# controller.net
KiCad netlist of a schematic drawn in EAGLE
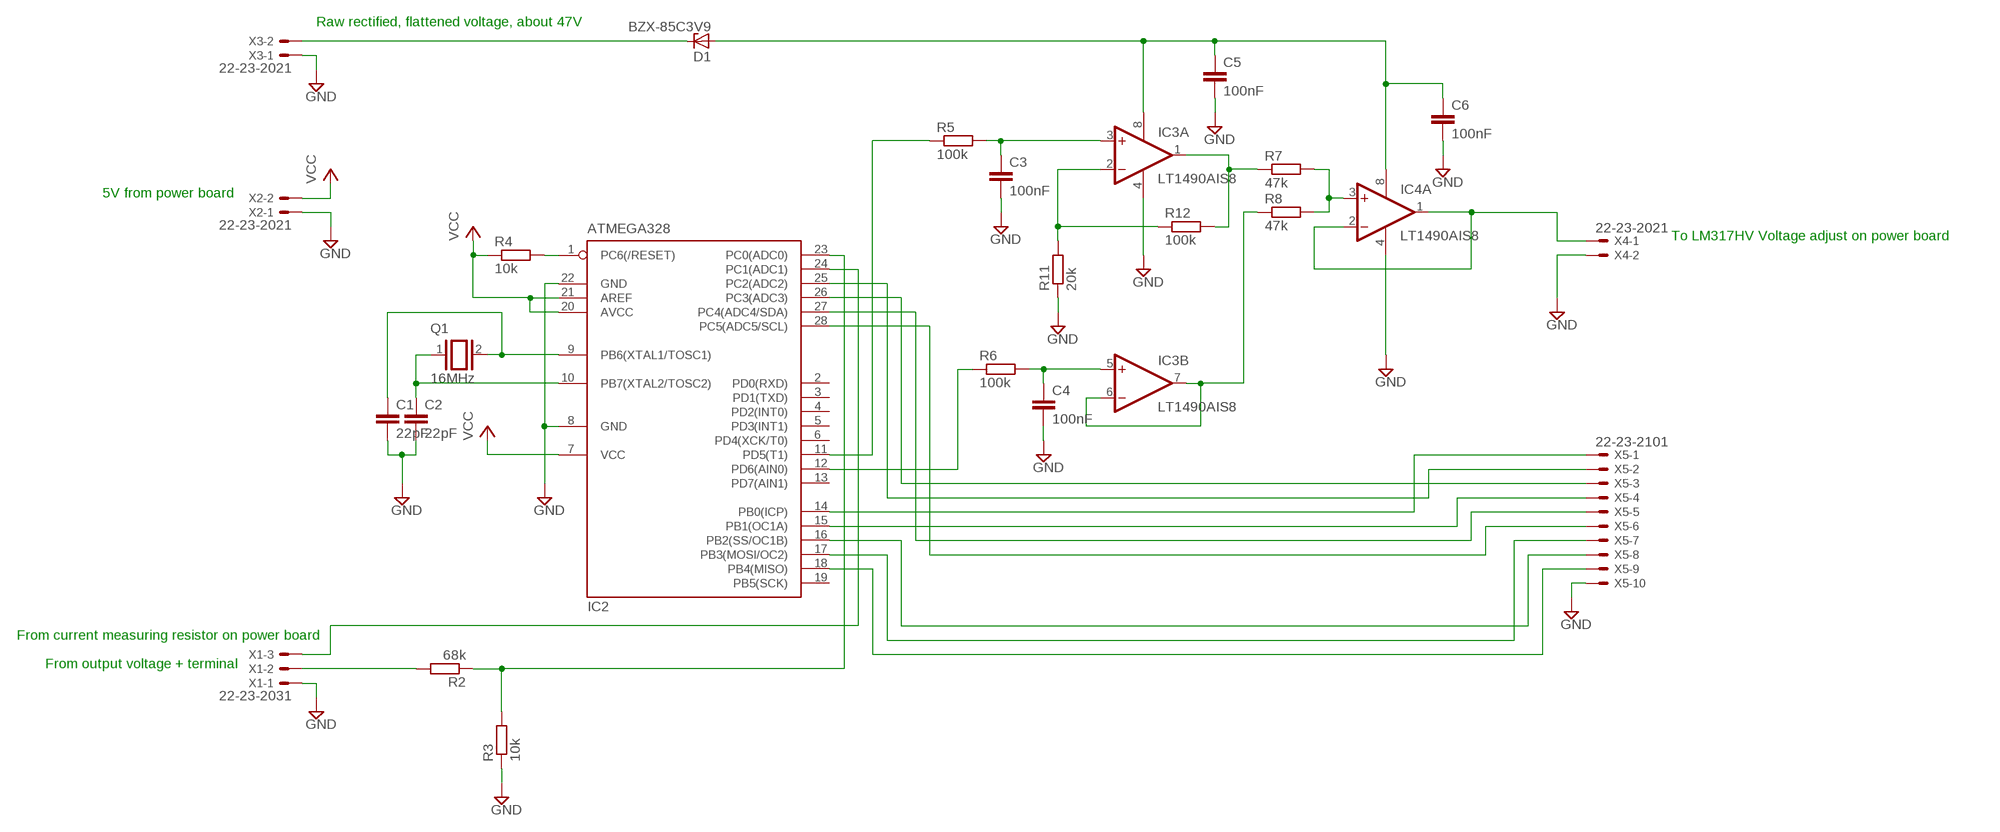
[diagram p0: schematic, sheet 1]

(export (version "E")
  (design (tool "Eeschema 10.0.6"))
  (components
    (comp (ref "C1")
      (value "22pF")
      (footprint "eagle-import:C2.5-2")
      (libsource (lib "eagle-import") (part "C2.5/2"))
    )
    (comp (ref "C2")
      (value "22pF")
      (footprint "eagle-import:C2.5-2")
      (libsource (lib "eagle-import") (part "C2.5/2"))
    )
    (comp (ref "C3")
      (value "100nF")
      (footprint "eagle-import:C7.5B3")
      (libsource (lib "eagle-import") (part "C7.5/3"))
    )
    (comp (ref "C4")
      (value "100nF")
      (footprint "eagle-import:C7.5B3")
      (libsource (lib "eagle-import") (part "C7.5/3"))
    )
    (comp (ref "C5")
      (value "100nF")
      (footprint "eagle-import:C7.5B3")
      (libsource (lib "eagle-import") (part "C7.5/3"))
    )
    (comp (ref "C6")
      (value "100nF")
      (footprint "eagle-import:C7.5B3")
      (libsource (lib "eagle-import") (part "C7.5/3"))
    )
    (comp (ref "D1")
      (value "BZX-85C3V9")
      (footprint "eagle-import:DO34Z7")
      (libsource (lib "eagle-import") (part "BZX90"))
    )
    (comp (ref "IC2")
      (value "ATMEGA328")
      (footprint "eagle-import:DIL28-3")
      (libsource (lib "eagle-import") (part "MEGA8-P"))
    )
    (comp (ref "IC3")
      (value "LT1490AIS8")
      (footprint "eagle-import:SO08")
      (libsource (lib "eagle-import") (part "OPA2UA134"))
    )
    (comp (ref "IC4")
      (value "LT1490AIS8")
      (footprint "eagle-import:SO08")
      (libsource (lib "eagle-import") (part "OPA2UA134"))
    )
    (comp (ref "Q1")
      (value "16MHz")
      (footprint "eagle-import:QS")
      (libsource (lib "eagle-import") (part "XTAL/S"))
    )
    (comp (ref "R2")
      (value "68k")
      (footprint "eagle-import:0207_10")
      (libsource (lib "eagle-import") (part "R-EU_0207/10"))
    )
    (comp (ref "R3")
      (value "10k")
      (footprint "eagle-import:0207_10")
      (libsource (lib "eagle-import") (part "R-EU_0207/10"))
    )
    (comp (ref "R4")
      (value "10k")
      (footprint "eagle-import:0207_10")
      (libsource (lib "eagle-import") (part "R-EU_0207/10"))
    )
    (comp (ref "R5")
      (value "100k")
      (footprint "eagle-import:0207_10")
      (libsource (lib "eagle-import") (part "R-EU_0207/10"))
    )
    (comp (ref "R6")
      (value "100k")
      (footprint "eagle-import:0207_10")
      (libsource (lib "eagle-import") (part "R-EU_0207/10"))
    )
    (comp (ref "R7")
      (value "47k")
      (footprint "eagle-import:0207_10")
      (libsource (lib "eagle-import") (part "R-EU_0207/10"))
    )
    (comp (ref "R8")
      (value "47k")
      (footprint "eagle-import:0207_10")
      (libsource (lib "eagle-import") (part "R-EU_0207/10"))
    )
    (comp (ref "R11")
      (value "20k")
      (footprint "eagle-import:0207_10")
      (libsource (lib "eagle-import") (part "R-EU_0207/10"))
    )
    (comp (ref "R12")
      (value "100k")
      (footprint "eagle-import:0207_10")
      (libsource (lib "eagle-import") (part "R-EU_0207/10"))
    )
    (comp (ref "X1")
      (value "22-23-2031")
      (footprint "eagle-import:22-23-2031")
      (fields (field (name "MF") "MOLEX"))
      (libsource (lib "eagle-import") (part "22-23-2031"))
    )
    (comp (ref "X2")
      (value "22-23-2021")
      (footprint "eagle-import:22-23-2021")
      (fields (field (name "MF") "MOLEX"))
      (libsource (lib "eagle-import") (part "22-23-2021"))
    )
    (comp (ref "X3")
      (value "22-23-2021")
      (footprint "eagle-import:22-23-2021")
      (fields (field (name "MF") "MOLEX"))
      (libsource (lib "eagle-import") (part "22-23-2021"))
    )
    (comp (ref "X4")
      (value "22-23-2021")
      (footprint "eagle-import:22-23-2021")
      (fields (field (name "MF") "MOLEX"))
      (libsource (lib "eagle-import") (part "22-23-2021"))
    )
    (comp (ref "X5")
      (value "22-23-2101")
      (footprint "eagle-import:22-23-2101")
      (fields (field (name "MF") "MOLEX"))
      (libsource (lib "eagle-import") (part "22-23-2101"))
    )
  )
  (nets
    (net (code "1") (name "GND") (class "Default")
      (node (ref "C1") (pin "2") (pinfunction "2_2") (pintype "passive"))
      (node (ref "C2") (pin "2") (pinfunction "2_2") (pintype "passive"))
      (node (ref "C3") (pin "2") (pinfunction "2_2") (pintype "passive"))
      (node (ref "C4") (pin "2") (pinfunction "2_2") (pintype "passive"))
      (node (ref "C5") (pin "2") (pinfunction "2_2") (pintype "passive"))
      (node (ref "C6") (pin "2") (pinfunction "2_2") (pintype "passive"))
      (node (ref "IC2") (pin "22") (pinfunction "GND_22") (pintype "power_in"))
      (node (ref "IC2") (pin "8") (pinfunction "GND_8") (pintype "power_in"))
      (node (ref "IC3") (pin "4") (pinfunction "V-_4") (pintype "power_in"))
      (node (ref "IC4") (pin "4") (pinfunction "V-_4") (pintype "power_in"))
      (node (ref "R11") (pin "1") (pinfunction "1_1") (pintype "passive"))
      (node (ref "R3") (pin "1") (pinfunction "1_1") (pintype "passive"))
      (node (ref "X1") (pin "1") (pinfunction "S_1") (pintype "passive"))
      (node (ref "X2") (pin "1") (pinfunction "S_1") (pintype "passive"))
      (node (ref "X3") (pin "1") (pinfunction "S_1") (pintype "passive"))
      (node (ref "X4") (pin "2") (pinfunction "S_2") (pintype "passive"))
      (node (ref "X5") (pin "10") (pinfunction "S_10") (pintype "passive"))
    )
    (net (code "2") (name "Net-(IC2-PB0(ICP))") (class "Default")
      (node (ref "IC2") (pin "14") (pinfunction "PB0(ICP)_14") (pintype "bidirectional"))
      (node (ref "X5") (pin "1") (pinfunction "S_1") (pintype "passive"))
    )
    (net (code "3") (name "Net-(IC2-PB1(OC1A))") (class "Default")
      (node (ref "IC2") (pin "15") (pinfunction "PB1(OC1A)_15") (pintype "bidirectional"))
      (node (ref "X5") (pin "4") (pinfunction "S_4") (pintype "passive"))
    )
    (net (code "4") (name "Net-(IC2-PB2(SS{slash}OC1B))") (class "Default")
      (node (ref "IC2") (pin "16") (pinfunction "PB2(SS/OC1B)_16") (pintype "bidirectional"))
      (node (ref "X5") (pin "8") (pinfunction "S_8") (pintype "passive"))
    )
    (net (code "5") (name "Net-(IC2-PB3(MOSI{slash}OC2))") (class "Default")
      (node (ref "IC2") (pin "17") (pinfunction "PB3(MOSI/OC2)_17") (pintype "bidirectional"))
      (node (ref "X5") (pin "7") (pinfunction "S_7") (pintype "passive"))
    )
    (net (code "6") (name "Net-(IC2-PB4(MISO))") (class "Default")
      (node (ref "IC2") (pin "18") (pinfunction "PB4(MISO)_18") (pintype "bidirectional"))
      (node (ref "X5") (pin "9") (pinfunction "S_9") (pintype "passive"))
    )
    (net (code "7") (name "Net-(IC2-PB6(XTAL1{slash}TOSC1))") (class "Default")
      (node (ref "C1") (pin "1") (pinfunction "1_1") (pintype "passive"))
      (node (ref "IC2") (pin "9") (pinfunction "PB6(XTAL1/TOSC1)_9") (pintype "bidirectional"))
      (node (ref "Q1") (pin "2") (pinfunction "2_2") (pintype "passive"))
    )
    (net (code "8") (name "Net-(IC2-PB7(XTAL2{slash}TOSC2))") (class "Default")
      (node (ref "C2") (pin "1") (pinfunction "1_1") (pintype "passive"))
      (node (ref "IC2") (pin "10") (pinfunction "PB7(XTAL2/TOSC2)_10") (pintype "bidirectional"))
      (node (ref "Q1") (pin "1") (pinfunction "1_1") (pintype "passive"))
    )
    (net (code "9") (name "Net-(IC2-PC0(ADC0))") (class "Default")
      (node (ref "IC2") (pin "23") (pinfunction "PC0(ADC0)_23") (pintype "bidirectional"))
      (node (ref "R2") (pin "1") (pinfunction "1_1") (pintype "passive"))
      (node (ref "R3") (pin "2") (pinfunction "2_2") (pintype "passive"))
    )
    (net (code "10") (name "Net-(IC2-PC1(ADC1))") (class "Default")
      (node (ref "IC2") (pin "24") (pinfunction "PC1(ADC1)_24") (pintype "bidirectional"))
      (node (ref "X1") (pin "3") (pinfunction "S_3") (pintype "passive"))
    )
    (net (code "11") (name "Net-(IC2-PC2(ADC2))") (class "Default")
      (node (ref "IC2") (pin "25") (pinfunction "PC2(ADC2)_25") (pintype "bidirectional"))
      (node (ref "X5") (pin "2") (pinfunction "S_2") (pintype "passive"))
    )
    (net (code "12") (name "Net-(IC2-PC3(ADC3))") (class "Default")
      (node (ref "IC2") (pin "26") (pinfunction "PC3(ADC3)_26") (pintype "bidirectional"))
      (node (ref "X5") (pin "3") (pinfunction "S_3") (pintype "passive"))
    )
    (net (code "13") (name "Net-(IC2-PC4(ADC4{slash}SDA))") (class "Default")
      (node (ref "IC2") (pin "27") (pinfunction "PC4(ADC4/SDA)_27") (pintype "bidirectional"))
      (node (ref "X5") (pin "5") (pinfunction "S_5") (pintype "passive"))
    )
    (net (code "14") (name "Net-(IC2-PC5(ADC5{slash}SCL))") (class "Default")
      (node (ref "IC2") (pin "28") (pinfunction "PC5(ADC5/SCL)_28") (pintype "bidirectional"))
      (node (ref "X5") (pin "6") (pinfunction "S_6") (pintype "passive"))
    )
    (net (code "15") (name "Net-(IC2-PC6({slash}RESET))") (class "Default")
      (node (ref "IC2") (pin "1") (pinfunction "PC6(/RESET)_1") (pintype "bidirectional"))
      (node (ref "R4") (pin "2") (pinfunction "2_2") (pintype "passive"))
    )
    (net (code "16") (name "Net-(IC2-PD5(T1))") (class "Default")
      (node (ref "IC2") (pin "11") (pinfunction "PD5(T1)_11") (pintype "bidirectional"))
      (node (ref "R5") (pin "1") (pinfunction "1_1") (pintype "passive"))
    )
    (net (code "17") (name "Net-(IC2-PD6(AIN0))") (class "Default")
      (node (ref "IC2") (pin "12") (pinfunction "PD6(AIN0)_12") (pintype "bidirectional"))
      (node (ref "R6") (pin "1") (pinfunction "1_1") (pintype "passive"))
    )
    (net (code "18") (name "Net-(IC3A-+IN)") (class "Default")
      (node (ref "C3") (pin "1") (pinfunction "1_1") (pintype "passive"))
      (node (ref "IC3") (pin "3") (pinfunction "+IN_3") (pintype "input"))
      (node (ref "R5") (pin "2") (pinfunction "2_2") (pintype "passive"))
    )
    (net (code "19") (name "Net-(IC3A--IN)") (class "Default")
      (node (ref "IC3") (pin "2") (pinfunction "-IN_2") (pintype "input"))
      (node (ref "R11") (pin "2") (pinfunction "2_2") (pintype "passive"))
      (node (ref "R12") (pin "1") (pinfunction "1_1") (pintype "passive"))
    )
    (net (code "20") (name "Net-(IC3A-OUT)") (class "Default")
      (node (ref "IC3") (pin "1") (pinfunction "OUT_1") (pintype "output"))
      (node (ref "R12") (pin "2") (pinfunction "2_2") (pintype "passive"))
      (node (ref "R7") (pin "1") (pinfunction "1_1") (pintype "passive"))
    )
    (net (code "21") (name "Net-(IC3A-V+)") (class "Default")
      (node (ref "C5") (pin "1") (pinfunction "1_1") (pintype "passive"))
      (node (ref "C6") (pin "1") (pinfunction "1_1") (pintype "passive"))
      (node (ref "D1") (pin "A") (pinfunction "A_A") (pintype "passive"))
      (node (ref "IC3") (pin "8") (pinfunction "V+_8") (pintype "power_in"))
      (node (ref "IC4") (pin "8") (pinfunction "V+_8") (pintype "power_in"))
    )
    (net (code "22") (name "Net-(IC3B-+IN)") (class "Default")
      (node (ref "C4") (pin "1") (pinfunction "1_1") (pintype "passive"))
      (node (ref "IC3") (pin "5") (pinfunction "+IN_5") (pintype "input"))
      (node (ref "R6") (pin "2") (pinfunction "2_2") (pintype "passive"))
    )
    (net (code "23") (name "Net-(IC3B--IN)") (class "Default")
      (node (ref "IC3") (pin "6") (pinfunction "-IN_6") (pintype "input"))
      (node (ref "IC3") (pin "7") (pinfunction "OUT_7") (pintype "output"))
      (node (ref "R8") (pin "1") (pinfunction "1_1") (pintype "passive"))
    )
    (net (code "24") (name "Net-(IC4A-+IN)") (class "Default")
      (node (ref "IC4") (pin "3") (pinfunction "+IN_3") (pintype "input"))
      (node (ref "R7") (pin "2") (pinfunction "2_2") (pintype "passive"))
      (node (ref "R8") (pin "2") (pinfunction "2_2") (pintype "passive"))
    )
    (net (code "25") (name "Net-(IC4A--IN)") (class "Default")
      (node (ref "IC4") (pin "1") (pinfunction "OUT_1") (pintype "output"))
      (node (ref "IC4") (pin "2") (pinfunction "-IN_2") (pintype "input"))
      (node (ref "X4") (pin "1") (pinfunction "S_1") (pintype "passive"))
    )
    (net (code "26") (name "Net-(X1B-S)") (class "Default")
      (node (ref "R2") (pin "2") (pinfunction "2_2") (pintype "passive"))
      (node (ref "X1") (pin "2") (pinfunction "S_2") (pintype "passive"))
    )
    (net (code "27") (name "Net-(X3B-S)") (class "Default")
      (node (ref "D1") (pin "C") (pinfunction "C_C") (pintype "passive"))
      (node (ref "X3") (pin "2") (pinfunction "S_2") (pintype "passive"))
    )
    (net (code "28") (name "VCC") (class "Default")
      (node (ref "IC2") (pin "20") (pinfunction "AVCC_20") (pintype "power_in"))
      (node (ref "IC2") (pin "21") (pinfunction "AREF_21") (pintype "passive"))
      (node (ref "IC2") (pin "7") (pinfunction "VCC_7") (pintype "power_in"))
      (node (ref "R4") (pin "1") (pinfunction "1_1") (pintype "passive"))
      (node (ref "X2") (pin "2") (pinfunction "S_2") (pintype "passive"))
    )
    (net (code "29") (name "unconnected-(IC2-PB5(SCK)-Pad19)") (class "Default")
      (node (ref "IC2") (pin "19") (pinfunction "PB5(SCK)_19") (pintype "bidirectional"))
    )
    (net (code "30") (name "unconnected-(IC2-PD0(RXD)-Pad2)") (class "Default")
      (node (ref "IC2") (pin "2") (pinfunction "PD0(RXD)_2") (pintype "bidirectional"))
    )
    (net (code "31") (name "unconnected-(IC2-PD1(TXD)-Pad3)") (class "Default")
      (node (ref "IC2") (pin "3") (pinfunction "PD1(TXD)_3") (pintype "bidirectional"))
    )
    (net (code "32") (name "unconnected-(IC2-PD2(INT0)-Pad4)") (class "Default")
      (node (ref "IC2") (pin "4") (pinfunction "PD2(INT0)_4") (pintype "bidirectional"))
    )
    (net (code "33") (name "unconnected-(IC2-PD3(INT1)-Pad5)") (class "Default")
      (node (ref "IC2") (pin "5") (pinfunction "PD3(INT1)_5") (pintype "bidirectional"))
    )
    (net (code "34") (name "unconnected-(IC2-PD4(XCK{slash}T0)-Pad6)") (class "Default")
      (node (ref "IC2") (pin "6") (pinfunction "PD4(XCK/T0)_6") (pintype "bidirectional"))
    )
    (net (code "35") (name "unconnected-(IC2-PD7(AIN1)-Pad13)") (class "Default")
      (node (ref "IC2") (pin "13") (pinfunction "PD7(AIN1)_13") (pintype "bidirectional"))
    )
  )
)
